# Sheet4.net
KiCad netlist of a schematic drawn in Altium Designer
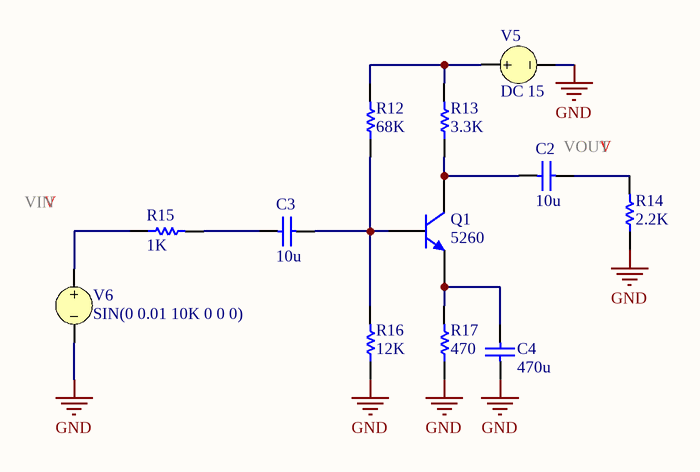
[diagram p0: Sheet4.SchDoc]

(export (version "E")
  (design (tool "Eeschema 10.0.6"))
  (components
    (comp (ref "C2")
      (value "10u")
      (description "Capacitor")
      (libsource (lib "Simulation Generic Components") (part "Capacitor"))
    )
    (comp (ref "C3")
      (value "10u")
      (description "Capacitor")
      (libsource (lib "Simulation Generic Components") (part "Capacitor"))
    )
    (comp (ref "C4")
      (value "470u")
      (description "Capacitor")
      (libsource (lib "Simulation Generic Components") (part "Capacitor"))
    )
    (comp (ref "Q1")
      (value "NPN")
      (footprint "SOT23_N")
      (description "NPN Switching Transistors")
      (fields (field (name "INFLOW") "5260") (field (name "VALIDATION") "Valid"))
      (libsource (lib "aKaReZa") (part "Semi_BJT_2N2222_SMD"))
    )
    (comp (ref "R12")
      (value "68K")
      (description "Resistor")
      (libsource (lib "Simulation Generic Components") (part "Resistor"))
    )
    (comp (ref "R13")
      (value "3.3K")
      (description "Resistor")
      (libsource (lib "Simulation Generic Components") (part "Resistor"))
    )
    (comp (ref "R14")
      (value "2.2K")
      (description "Resistor")
      (libsource (lib "Simulation Generic Components") (part "Resistor"))
    )
    (comp (ref "R15")
      (value "1K")
      (description "Resistor")
      (libsource (lib "Simulation Generic Components") (part "Resistor"))
    )
    (comp (ref "R16")
      (value "12K")
      (description "Resistor")
      (libsource (lib "Simulation Generic Components") (part "Resistor"))
    )
    (comp (ref "R17")
      (value "470")
      (description "Resistor")
      (libsource (lib "Simulation Generic Components") (part "Resistor"))
    )
    (comp (ref "V5")
      (value "DC 15")
      (description "Voltage Source")
      (fields (field (name "PUBLISHER") "Altium Limited"))
      (libsource (lib "Simulation Generic Components") (part "VSRC"))
    )
    (comp (ref "V6")
      (value "SIN(0 0.01 10K 0 0 0)")
      (description "Voltage Source")
      (fields (field (name "PUBLISHER") "Altium Limited"))
      (libsource (lib "Simulation Generic Components") (part "VSRC"))
    )
  )
  (nets
    (net (code "1") (name "GND") (class "Default")
      (node (ref "C4") (pin "1") (pinfunction "1_1") (pintype "passive"))
      (node (ref "R14") (pin "1") (pinfunction "1_1") (pintype "passive"))
      (node (ref "R16") (pin "1") (pinfunction "1_1") (pintype "passive"))
      (node (ref "R17") (pin "1") (pinfunction "1_1") (pintype "passive"))
      (node (ref "V5") (pin "2") (pinfunction "2_2") (pintype "passive"))
      (node (ref "V6") (pin "2") (pinfunction "2_2") (pintype "passive"))
    )
    (net (code "2") (name "Net-(C2-Pad1)") (class "Default")
      (node (ref "C2") (pin "1") (pinfunction "1_1") (pintype "passive"))
      (node (ref "R14") (pin "2") (pinfunction "2_2") (pintype "passive"))
    )
    (net (code "3") (name "Net-(C3-Pad1)") (class "Default")
      (node (ref "C3") (pin "1") (pinfunction "1_1") (pintype "passive"))
      (node (ref "R15") (pin "2") (pinfunction "2_2") (pintype "passive"))
    )
    (net (code "4") (name "Net-(Q1-B)") (class "Default")
      (node (ref "C3") (pin "2") (pinfunction "2_2") (pintype "passive"))
      (node (ref "Q1") (pin "1") (pinfunction "B_1") (pintype "passive"))
      (node (ref "R12") (pin "1") (pinfunction "1_1") (pintype "passive"))
      (node (ref "R16") (pin "2") (pinfunction "2_2") (pintype "passive"))
    )
    (net (code "5") (name "Net-(Q1-C)") (class "Default")
      (node (ref "C2") (pin "2") (pinfunction "2_2") (pintype "passive"))
      (node (ref "Q1") (pin "3") (pinfunction "C_3") (pintype "passive"))
      (node (ref "R13") (pin "1") (pinfunction "1_1") (pintype "passive"))
    )
    (net (code "6") (name "Net-(Q1-E)") (class "Default")
      (node (ref "C4") (pin "2") (pinfunction "2_2") (pintype "passive"))
      (node (ref "Q1") (pin "2") (pinfunction "E_2") (pintype "passive"))
      (node (ref "R17") (pin "2") (pinfunction "2_2") (pintype "passive"))
    )
    (net (code "7") (name "Net-(R12-Pad2)") (class "Default")
      (node (ref "R12") (pin "2") (pinfunction "2_2") (pintype "passive"))
      (node (ref "R13") (pin "2") (pinfunction "2_2") (pintype "passive"))
      (node (ref "V5") (pin "1") (pinfunction "1_1") (pintype "passive"))
    )
    (net (code "8") (name "Net-(R15-Pad1)") (class "Default")
      (node (ref "R15") (pin "1") (pinfunction "1_1") (pintype "passive"))
      (node (ref "V6") (pin "1") (pinfunction "1_1") (pintype "passive"))
    )
  )
)
